# Sheet1.net
KiCad netlist of a schematic drawn in Altium Designer
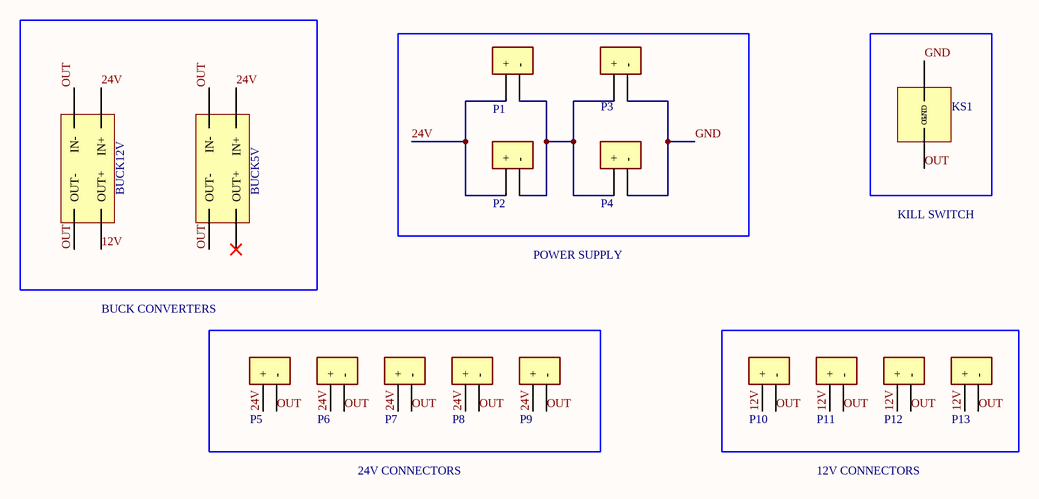
[diagram p0: Sheet1.SchDoc]

(export (version "E")
  (design (tool "Eeschema 10.0.6"))
  (components
    (comp (ref "BUCK5V") (value "BUCK") (footprint "BUCK") (libsource (lib "Schlib1") (part "BUCK")))
    (comp (ref "BUCK12V") (value "BUCK") (footprint "BUCK") (libsource (lib "Schlib1") (part "BUCK")))
    (comp (ref "KS1") (value "KS") (footprint "KS") (libsource (lib "Schlib1") (part "KS")))
    (comp (ref "P1")
      (value "282837-2")
      (footprint "TE_282837-2")
      (fields (field (name "MF") "TE Connectivity"))
      (libsource (lib "282837-2") (part "282837-2"))
    )
    (comp (ref "P2")
      (value "282837-2")
      (footprint "TE_282837-2")
      (fields (field (name "MF") "TE Connectivity"))
      (libsource (lib "282837-2") (part "282837-2"))
    )
    (comp (ref "P3")
      (value "282837-2")
      (footprint "TE_282837-2")
      (fields (field (name "MF") "TE Connectivity"))
      (libsource (lib "282837-2") (part "282837-2"))
    )
    (comp (ref "P4")
      (value "282837-2")
      (footprint "TE_282837-2")
      (fields (field (name "MF") "TE Connectivity"))
      (libsource (lib "282837-2") (part "282837-2"))
    )
    (comp (ref "P5")
      (value "282837-2")
      (footprint "TE_282837-2")
      (fields (field (name "MF") "TE Connectivity"))
      (libsource (lib "282837-2") (part "282837-2"))
    )
    (comp (ref "P6")
      (value "282837-2")
      (footprint "TE_282837-2")
      (fields (field (name "MF") "TE Connectivity"))
      (libsource (lib "282837-2") (part "282837-2"))
    )
    (comp (ref "P7")
      (value "282837-2")
      (footprint "TE_282837-2")
      (fields (field (name "MF") "TE Connectivity"))
      (libsource (lib "282837-2") (part "282837-2"))
    )
    (comp (ref "P8")
      (value "282837-2")
      (footprint "TE_282837-2")
      (fields (field (name "MF") "TE Connectivity"))
      (libsource (lib "282837-2") (part "282837-2"))
    )
    (comp (ref "P9")
      (value "282837-2")
      (footprint "TE_282837-2")
      (fields (field (name "MF") "TE Connectivity"))
      (libsource (lib "282837-2") (part "282837-2"))
    )
    (comp (ref "P10")
      (value "282837-2")
      (footprint "TE_282837-2")
      (fields (field (name "MF") "TE Connectivity"))
      (libsource (lib "282837-2") (part "282837-2"))
    )
    (comp (ref "P11")
      (value "282837-2")
      (footprint "TE_282837-2")
      (fields (field (name "MF") "TE Connectivity"))
      (libsource (lib "282837-2") (part "282837-2"))
    )
    (comp (ref "P12")
      (value "282837-2")
      (footprint "TE_282837-2")
      (fields (field (name "MF") "TE Connectivity"))
      (libsource (lib "282837-2") (part "282837-2"))
    )
    (comp (ref "P13")
      (value "282837-2")
      (footprint "TE_282837-2")
      (fields (field (name "MF") "TE Connectivity"))
      (libsource (lib "282837-2") (part "282837-2"))
    )
  )
  (nets
    (net (code "1") (name "/12V") (class "Default")
      (node (ref "BUCK12V") (pin "3") (pinfunction "OUT+_3") (pintype "passive"))
      (node (ref "P10") (pin "1") (pinfunction "+_1") (pintype "passive"))
      (node (ref "P11") (pin "1") (pinfunction "+_1") (pintype "passive"))
      (node (ref "P12") (pin "1") (pinfunction "+_1") (pintype "passive"))
      (node (ref "P13") (pin "1") (pinfunction "+_1") (pintype "passive"))
    )
    (net (code "2") (name "/24V") (class "Default")
      (node (ref "BUCK12V") (pin "1") (pinfunction "IN+_1") (pintype "passive"))
      (node (ref "BUCK5V") (pin "1") (pinfunction "IN+_1") (pintype "passive"))
      (node (ref "P1") (pin "1") (pinfunction "+_1") (pintype "passive"))
      (node (ref "P2") (pin "1") (pinfunction "+_1") (pintype "passive"))
      (node (ref "P5") (pin "1") (pinfunction "+_1") (pintype "passive"))
      (node (ref "P6") (pin "1") (pinfunction "+_1") (pintype "passive"))
      (node (ref "P7") (pin "1") (pinfunction "+_1") (pintype "passive"))
      (node (ref "P8") (pin "1") (pinfunction "+_1") (pintype "passive"))
      (node (ref "P9") (pin "1") (pinfunction "+_1") (pintype "passive"))
    )
    (net (code "3") (name "/GND") (class "Default")
      (node (ref "KS1") (pin "2") (pinfunction "GND_2") (pintype "passive"))
      (node (ref "P3") (pin "2") (pinfunction "-_2") (pintype "passive"))
      (node (ref "P4") (pin "2") (pinfunction "-_2") (pintype "passive"))
    )
    (net (code "4") (name "/OUT") (class "Default")
      (node (ref "BUCK12V") (pin "2") (pinfunction "IN-_2") (pintype "passive"))
      (node (ref "BUCK12V") (pin "4") (pinfunction "OUT-_4") (pintype "passive"))
      (node (ref "BUCK5V") (pin "2") (pinfunction "IN-_2") (pintype "passive"))
      (node (ref "BUCK5V") (pin "4") (pinfunction "OUT-_4") (pintype "passive"))
      (node (ref "KS1") (pin "1") (pinfunction "OUT_1") (pintype "passive"))
      (node (ref "P10") (pin "2") (pinfunction "-_2") (pintype "passive"))
      (node (ref "P11") (pin "2") (pinfunction "-_2") (pintype "passive"))
      (node (ref "P12") (pin "2") (pinfunction "-_2") (pintype "passive"))
      (node (ref "P13") (pin "2") (pinfunction "-_2") (pintype "passive"))
      (node (ref "P5") (pin "2") (pinfunction "-_2") (pintype "passive"))
      (node (ref "P6") (pin "2") (pinfunction "-_2") (pintype "passive"))
      (node (ref "P7") (pin "2") (pinfunction "-_2") (pintype "passive"))
      (node (ref "P8") (pin "2") (pinfunction "-_2") (pintype "passive"))
      (node (ref "P9") (pin "2") (pinfunction "-_2") (pintype "passive"))
    )
    (net (code "5") (name "Net-(P1--)") (class "Default")
      (node (ref "P1") (pin "2") (pinfunction "-_2") (pintype "passive"))
      (node (ref "P2") (pin "2") (pinfunction "-_2") (pintype "passive"))
      (node (ref "P3") (pin "1") (pinfunction "+_1") (pintype "passive"))
      (node (ref "P4") (pin "1") (pinfunction "+_1") (pintype "passive"))
    )
    (net (code "6") (name "unconnected-(BUCK5V-OUT+-Pad3)") (class "Default")
      (node (ref "BUCK5V") (pin "3") (pinfunction "OUT+_3") (pintype "passive+no_connect"))
    )
  )
)
